# PCB_3U_DAC.net
KiCad netlist of a schematic drawn in Altium Designer
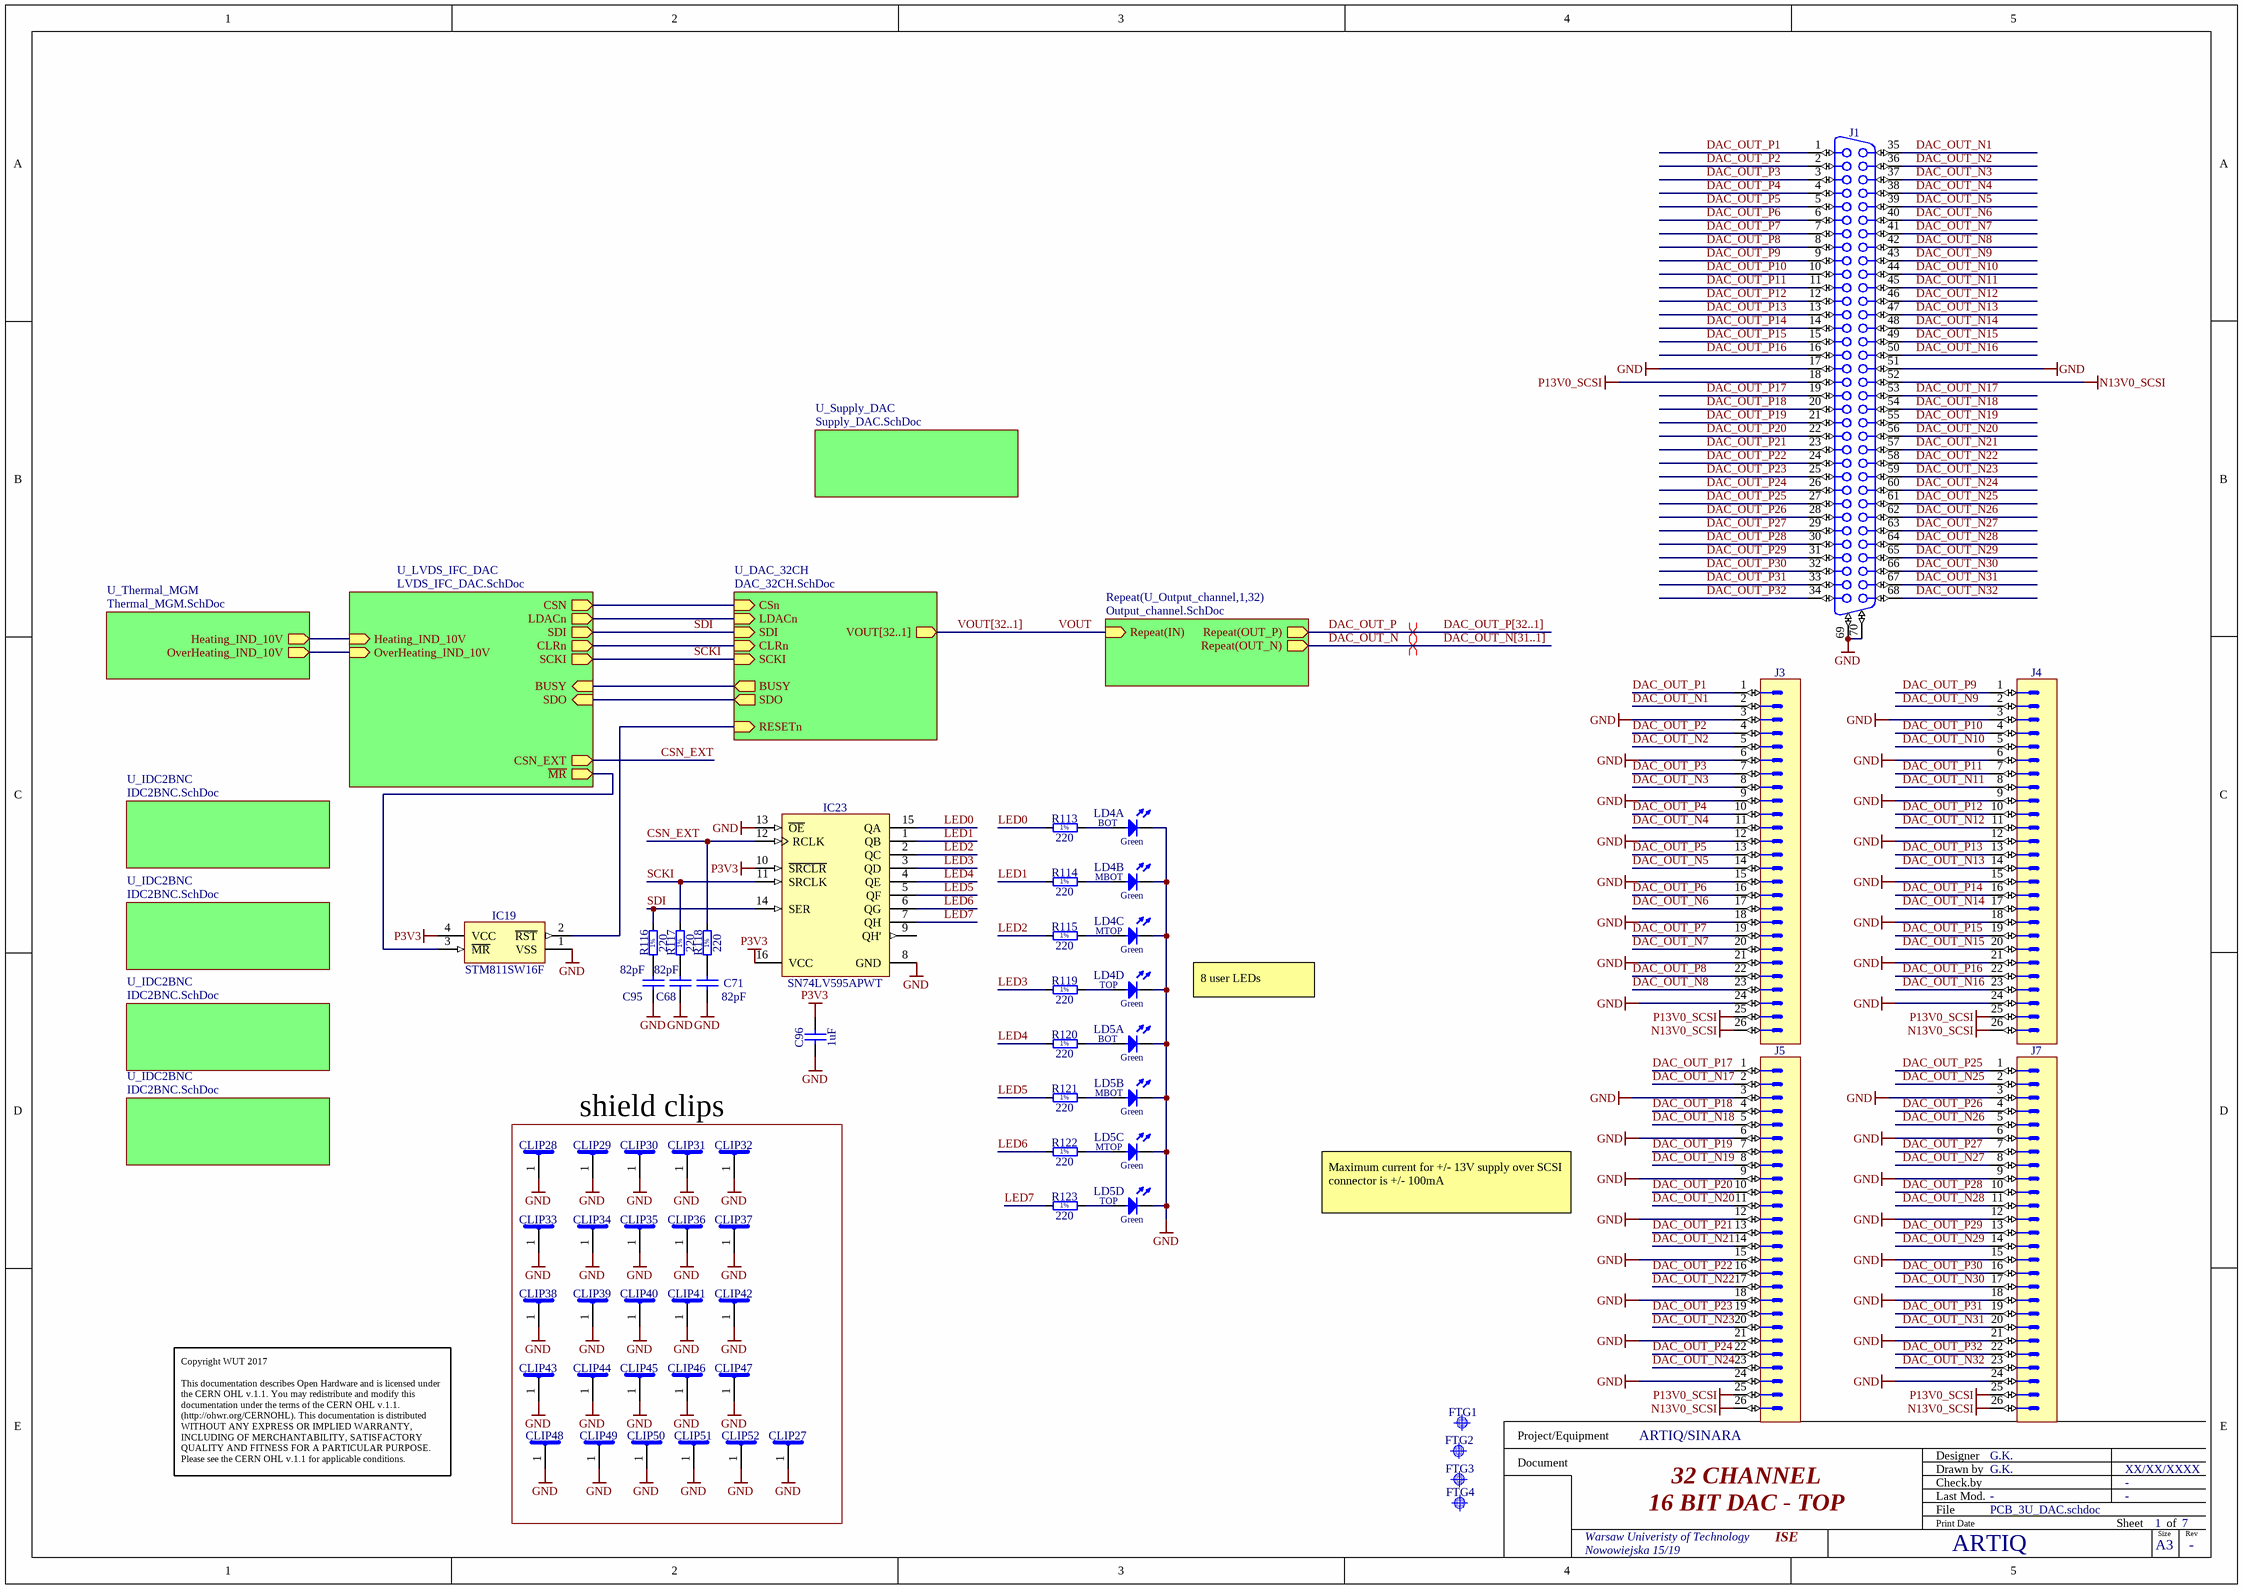
[diagram p0: PCB_3U_DAC.schdoc]

(export (version "E")
  (design (tool "Eeschema 10.0.6"))
  (components
    (comp (ref "C68")
      (value "82pF")
      (footprint "CAPC1608X87N")
      (description "Non-polarised capacitor")
      (fields
        (field (name "PART NUMBER") "CC0603_82PF_50V_5%_NP0")
        (field (name "VOLTAGE") "50V")
        (field (name "AUTHOR") "CERN DEM JLC")
      )
      (libsource (lib "Capacitors") (part "Capacitor - non polarized"))
    )
    (comp (ref "C71")
      (value "82pF")
      (footprint "CAPC1608X87N")
      (description "Non-polarised capacitor")
      (fields
        (field (name "PART NUMBER") "CC0603_82PF_50V_5%_NP0")
        (field (name "VOLTAGE") "50V")
        (field (name "AUTHOR") "CERN DEM JLC")
      )
      (libsource (lib "Capacitors") (part "Capacitor - non polarized"))
    )
    (comp (ref "C95")
      (value "82pF")
      (footprint "CAPC1608X87N")
      (description "Non-polarised capacitor")
      (fields
        (field (name "PART NUMBER") "CC0603_82PF_50V_5%_NP0")
        (field (name "VOLTAGE") "50V")
        (field (name "AUTHOR") "CERN DEM JLC")
      )
      (libsource (lib "Capacitors") (part "Capacitor - non polarized"))
    )
    (comp (ref "C96")
      (value "1uF")
      (footprint "CAPC1608X87N")
      (description "Non-polarised capacitor")
      (fields
        (field (name "PART NUMBER") "CC0603_1UF_25V_10%_X7R")
        (field (name "VOLTAGE") "25V")
        (field (name "AUTHOR") "CERN DEM JLC")
      )
      (libsource (lib "Capacitors") (part "Capacitor - non polarized"))
    )
    (comp (ref "CLIP27")
      (value "S1411-46R")
      (footprint "CLIP_HOLLAND-SHIELDING_LC")
      (description "Surface Mount Clip for PCB Screening Covers")
      (fields (field (name "MANUFACTURER") "HARWIN") (field (name "AUTHOR") "CERN DEM JLC"))
      (libsource (lib "LIBRARY_SCH") (part "SHIELD_CLIP"))
    )
    (comp (ref "CLIP28")
      (value "S1411-46R")
      (footprint "CLIP_HOLLAND-SHIELDING_LC")
      (description "Surface Mount Clip for PCB Screening Covers")
      (fields (field (name "MANUFACTURER") "HARWIN") (field (name "AUTHOR") "CERN DEM JLC"))
      (libsource (lib "LIBRARY_SCH") (part "SHIELD_CLIP"))
    )
    (comp (ref "CLIP29")
      (value "S1411-46R")
      (footprint "CLIP_HOLLAND-SHIELDING_LC")
      (description "Surface Mount Clip for PCB Screening Covers")
      (fields (field (name "MANUFACTURER") "HARWIN") (field (name "AUTHOR") "CERN DEM JLC"))
      (libsource (lib "LIBRARY_SCH") (part "SHIELD_CLIP"))
    )
    (comp (ref "CLIP30")
      (value "S1411-46R")
      (footprint "CLIP_HOLLAND-SHIELDING_LC")
      (description "Surface Mount Clip for PCB Screening Covers")
      (fields (field (name "MANUFACTURER") "HARWIN") (field (name "AUTHOR") "CERN DEM JLC"))
      (libsource (lib "LIBRARY_SCH") (part "SHIELD_CLIP"))
    )
    (comp (ref "CLIP31")
      (value "S1411-46R")
      (footprint "CLIP_HOLLAND-SHIELDING_LC")
      (description "Surface Mount Clip for PCB Screening Covers")
      (fields (field (name "MANUFACTURER") "HARWIN") (field (name "AUTHOR") "CERN DEM JLC"))
      (libsource (lib "LIBRARY_SCH") (part "SHIELD_CLIP"))
    )
    (comp (ref "CLIP32")
      (value "S1411-46R")
      (footprint "CLIP_HOLLAND-SHIELDING_LC")
      (description "Surface Mount Clip for PCB Screening Covers")
      (fields (field (name "MANUFACTURER") "HARWIN") (field (name "AUTHOR") "CERN DEM JLC"))
      (libsource (lib "LIBRARY_SCH") (part "SHIELD_CLIP"))
    )
    (comp (ref "CLIP33")
      (value "S1411-46R")
      (footprint "CLIP_HOLLAND-SHIELDING_LC")
      (description "Surface Mount Clip for PCB Screening Covers")
      (fields (field (name "MANUFACTURER") "HARWIN") (field (name "AUTHOR") "CERN DEM JLC"))
      (libsource (lib "LIBRARY_SCH") (part "SHIELD_CLIP"))
    )
    (comp (ref "CLIP34")
      (value "S1411-46R")
      (footprint "CLIP_HOLLAND-SHIELDING_LC")
      (description "Surface Mount Clip for PCB Screening Covers")
      (fields (field (name "MANUFACTURER") "HARWIN") (field (name "AUTHOR") "CERN DEM JLC"))
      (libsource (lib "LIBRARY_SCH") (part "SHIELD_CLIP"))
    )
    (comp (ref "CLIP35")
      (value "S1411-46R")
      (footprint "CLIP_HOLLAND-SHIELDING_LC")
      (description "Surface Mount Clip for PCB Screening Covers")
      (fields (field (name "MANUFACTURER") "HARWIN") (field (name "AUTHOR") "CERN DEM JLC"))
      (libsource (lib "LIBRARY_SCH") (part "SHIELD_CLIP"))
    )
    (comp (ref "CLIP36")
      (value "S1411-46R")
      (footprint "CLIP_HOLLAND-SHIELDING_LC")
      (description "Surface Mount Clip for PCB Screening Covers")
      (fields (field (name "MANUFACTURER") "HARWIN") (field (name "AUTHOR") "CERN DEM JLC"))
      (libsource (lib "LIBRARY_SCH") (part "SHIELD_CLIP"))
    )
    (comp (ref "CLIP37")
      (value "S1411-46R")
      (footprint "CLIP_HOLLAND-SHIELDING_LC")
      (description "Surface Mount Clip for PCB Screening Covers")
      (fields (field (name "MANUFACTURER") "HARWIN") (field (name "AUTHOR") "CERN DEM JLC"))
      (libsource (lib "LIBRARY_SCH") (part "SHIELD_CLIP"))
    )
    (comp (ref "CLIP38")
      (value "S1411-46R")
      (footprint "CLIP_HOLLAND-SHIELDING_LC")
      (description "Surface Mount Clip for PCB Screening Covers")
      (fields (field (name "MANUFACTURER") "HARWIN") (field (name "AUTHOR") "CERN DEM JLC"))
      (libsource (lib "LIBRARY_SCH") (part "SHIELD_CLIP"))
    )
    (comp (ref "CLIP39")
      (value "S1411-46R")
      (footprint "CLIP_HOLLAND-SHIELDING_LC")
      (description "Surface Mount Clip for PCB Screening Covers")
      (fields (field (name "MANUFACTURER") "HARWIN") (field (name "AUTHOR") "CERN DEM JLC"))
      (libsource (lib "LIBRARY_SCH") (part "SHIELD_CLIP"))
    )
    (comp (ref "CLIP40")
      (value "S1411-46R")
      (footprint "CLIP_HOLLAND-SHIELDING_LC")
      (description "Surface Mount Clip for PCB Screening Covers")
      (fields (field (name "MANUFACTURER") "HARWIN") (field (name "AUTHOR") "CERN DEM JLC"))
      (libsource (lib "LIBRARY_SCH") (part "SHIELD_CLIP"))
    )
    (comp (ref "CLIP41")
      (value "S1411-46R")
      (footprint "CLIP_HOLLAND-SHIELDING_LC")
      (description "Surface Mount Clip for PCB Screening Covers")
      (fields (field (name "MANUFACTURER") "HARWIN") (field (name "AUTHOR") "CERN DEM JLC"))
      (libsource (lib "LIBRARY_SCH") (part "SHIELD_CLIP"))
    )
    (comp (ref "CLIP42")
      (value "S1411-46R")
      (footprint "CLIP_HOLLAND-SHIELDING_LC")
      (description "Surface Mount Clip for PCB Screening Covers")
      (fields (field (name "MANUFACTURER") "HARWIN") (field (name "AUTHOR") "CERN DEM JLC"))
      (libsource (lib "LIBRARY_SCH") (part "SHIELD_CLIP"))
    )
    (comp (ref "CLIP43")
      (value "S1411-46R")
      (footprint "CLIP_HOLLAND-SHIELDING_LC")
      (description "Surface Mount Clip for PCB Screening Covers")
      (fields (field (name "MANUFACTURER") "HARWIN") (field (name "AUTHOR") "CERN DEM JLC"))
      (libsource (lib "LIBRARY_SCH") (part "SHIELD_CLIP"))
    )
    (comp (ref "CLIP44")
      (value "S1411-46R")
      (footprint "CLIP_HOLLAND-SHIELDING_LC")
      (description "Surface Mount Clip for PCB Screening Covers")
      (fields (field (name "MANUFACTURER") "HARWIN") (field (name "AUTHOR") "CERN DEM JLC"))
      (libsource (lib "LIBRARY_SCH") (part "SHIELD_CLIP"))
    )
    (comp (ref "CLIP45")
      (value "S1411-46R")
      (footprint "CLIP_HOLLAND-SHIELDING_LC")
      (description "Surface Mount Clip for PCB Screening Covers")
      (fields (field (name "MANUFACTURER") "HARWIN") (field (name "AUTHOR") "CERN DEM JLC"))
      (libsource (lib "LIBRARY_SCH") (part "SHIELD_CLIP"))
    )
    (comp (ref "CLIP46")
      (value "S1411-46R")
      (footprint "CLIP_HOLLAND-SHIELDING_LC")
      (description "Surface Mount Clip for PCB Screening Covers")
      (fields (field (name "MANUFACTURER") "HARWIN") (field (name "AUTHOR") "CERN DEM JLC"))
      (libsource (lib "LIBRARY_SCH") (part "SHIELD_CLIP"))
    )
    (comp (ref "CLIP47")
      (value "S1411-46R")
      (footprint "CLIP_HOLLAND-SHIELDING_LC")
      (description "Surface Mount Clip for PCB Screening Covers")
      (fields (field (name "MANUFACTURER") "HARWIN") (field (name "AUTHOR") "CERN DEM JLC"))
      (libsource (lib "LIBRARY_SCH") (part "SHIELD_CLIP"))
    )
    (comp (ref "CLIP48")
      (value "S1411-46R")
      (footprint "CLIP_HOLLAND-SHIELDING_LC")
      (description "Surface Mount Clip for PCB Screening Covers")
      (fields (field (name "MANUFACTURER") "HARWIN") (field (name "AUTHOR") "CERN DEM JLC"))
      (libsource (lib "LIBRARY_SCH") (part "SHIELD_CLIP"))
    )
    (comp (ref "CLIP49")
      (value "S1411-46R")
      (footprint "CLIP_HOLLAND-SHIELDING_LC")
      (description "Surface Mount Clip for PCB Screening Covers")
      (fields (field (name "MANUFACTURER") "HARWIN") (field (name "AUTHOR") "CERN DEM JLC"))
      (libsource (lib "LIBRARY_SCH") (part "SHIELD_CLIP"))
    )
    (comp (ref "CLIP50")
      (value "S1411-46R")
      (footprint "CLIP_HOLLAND-SHIELDING_LC")
      (description "Surface Mount Clip for PCB Screening Covers")
      (fields (field (name "MANUFACTURER") "HARWIN") (field (name "AUTHOR") "CERN DEM JLC"))
      (libsource (lib "LIBRARY_SCH") (part "SHIELD_CLIP"))
    )
    (comp (ref "CLIP51")
      (value "S1411-46R")
      (footprint "CLIP_HOLLAND-SHIELDING_LC")
      (description "Surface Mount Clip for PCB Screening Covers")
      (fields (field (name "MANUFACTURER") "HARWIN") (field (name "AUTHOR") "CERN DEM JLC"))
      (libsource (lib "LIBRARY_SCH") (part "SHIELD_CLIP"))
    )
    (comp (ref "CLIP52")
      (value "S1411-46R")
      (footprint "CLIP_HOLLAND-SHIELDING_LC")
      (description "Surface Mount Clip for PCB Screening Covers")
      (fields (field (name "MANUFACTURER") "HARWIN") (field (name "AUTHOR") "CERN DEM JLC"))
      (libsource (lib "LIBRARY_SCH") (part "SHIELD_CLIP"))
    )
    (comp (ref "FTG1")
      (value "Use only in PCB")
      (footprint "FIDUCIAL_TOP_C100-200")
      (description "Fiducial Target")
      (fields (field (name "PART NUMBER") "FIDUCIAL_TARGET_C100-200") (field (name "AUTHOR") "CERN DEM JLC"))
      (libsource (lib "Eletro-mechanical") (part "Fiducial Target"))
    )
    (comp (ref "FTG2")
      (value "Use only in PCB")
      (footprint "FIDUCIAL_TOP_S100-200")
      (description "Fiducial Target")
      (fields (field (name "PART NUMBER") "FIDUCIAL_TARGET_S100-200") (field (name "AUTHOR") "CERN DEM JLC"))
      (libsource (lib "Eletro-mechanical") (part "Fiducial Target"))
    )
    (comp (ref "FTG3")
      (value "Use only in PCB")
      (footprint "FIDUCIAL_TOP_S200-400")
      (description "Fiducial Target")
      (fields (field (name "PART NUMBER") "FIDUCIAL_TARGET_S200-400") (field (name "AUTHOR") "CERN DEM JLC"))
      (libsource (lib "Eletro-mechanical") (part "Fiducial Target"))
    )
    (comp (ref "FTG4")
      (value "Use only in PCB")
      (footprint "FIDUCIAL_TOP_S100-200")
      (description "Fiducial Target")
      (fields (field (name "PART NUMBER") "FIDUCIAL_TARGET_S100-200") (field (name "AUTHOR") "CERN DEM JLC"))
      (libsource (lib "Eletro-mechanical") (part "Fiducial Target"))
    )
    (comp (ref "IC19")
      (value "STM811SW16F")
      (footprint "SOT143N")
      (description "Microprocessor Reset Circuit")
      (fields (field (name "MANUFACTURER") "ST MICROELECTRONICS") (field (name "AUTHOR") "CERN DEM JLC"))
      (libsource (lib "ICs And Semiconductors") (part "STM811"))
    )
    (comp (ref "IC23")
      (value "SN74LV595APWT")
      (footprint "SOP65P640X120-16N")
      (description "8-Bit Shift Register With 3-State Output Register")
      (fields (field (name "MANUFACTURER") "TEXAS INSTRUMENTS") (field (name "AUTHOR") "CERN DEM JLC"))
      (libsource (lib "ICs And Semiconductors") (part "74595"))
    )
    (comp (ref "J1")
      (value "D-SUB")
      (footprint "TYCO_5787082-7")
      (description "68 contacts, AMPLIMITE .050\", Right Angled Receptacle Series III")
      (fields
        (field (name "PART NUMBER") "TYCO_5787082-7")
        (field (name "MANUFACTURER") "TYCO ELECTRONICS")
        (field (name "AUTHOR") "CERN DEM JLC")
      )
      (libsource (lib "Connectors") (part "TYCO_5787082-7"))
    )
    (comp (ref "J3")
      (value "Header 26")
      (footprint "3M_N2526-6002RB")
      (description "Connector 26 Male")
      (fields
        (field (name "PART NUMBER") "3M_N2526-6002RB")
        (field (name "MANUFACTURER") "3M")
        (field (name "AUTHOR") "CERN DEM JLC")
      )
      (libsource (lib "Connectors") (part "Connector 26 Male"))
    )
    (comp (ref "J4")
      (value "Header 26")
      (footprint "3M_N2526-6002RB")
      (description "Connector 26 Male")
      (fields
        (field (name "PART NUMBER") "3M_N2526-6002RB")
        (field (name "MANUFACTURER") "3M")
        (field (name "AUTHOR") "CERN DEM JLC")
      )
      (libsource (lib "Connectors") (part "Connector 26 Male"))
    )
    (comp (ref "J5")
      (value "Header 26")
      (footprint "3M_N2526-6002RB")
      (description "Connector 26 Male")
      (fields
        (field (name "PART NUMBER") "3M_N2526-6002RB")
        (field (name "MANUFACTURER") "3M")
        (field (name "AUTHOR") "CERN DEM JLC")
      )
      (libsource (lib "Connectors") (part "Connector 26 Male"))
    )
    (comp (ref "J7")
      (value "Header 26")
      (footprint "3M_N2526-6002RB")
      (description "Connector 26 Male")
      (fields
        (field (name "PART NUMBER") "3M_N2526-6002RB")
        (field (name "MANUFACTURER") "3M")
        (field (name "AUTHOR") "CERN DEM JLC")
      )
      (libsource (lib "Connectors") (part "Connector 26 Male"))
    )
    (comp (ref "LD4")
      (value "Green")
      (footprint "LED_BIVAR_H485CGDL")
      (description "LED x4 Green 1C2A-BOT_3C4A_5C6A_7C8A-TOP")
      (fields
        (field (name "PART NUMBER") "LED_BIVAR_H485CGDL")
        (field (name "MANUFACTURER") "BIVAR")
        (field (name "AUTHOR") "CERN DEM JLC")
      )
      (libsource (lib "ICs And Semiconductors") (part "LED x4 Green 1C2A-BOT_3C4A_5C6A_7C8A-TOP"))
    )
    (comp (ref "LD5")
      (value "Green")
      (footprint "LED_BIVAR_H485CGDL")
      (description "LED x4 Green 1C2A-BOT_3C4A_5C6A_7C8A-TOP")
      (fields
        (field (name "PART NUMBER") "LED_BIVAR_H485CGDL")
        (field (name "MANUFACTURER") "BIVAR")
        (field (name "AUTHOR") "CERN DEM JLC")
      )
      (libsource (lib "ICs And Semiconductors") (part "LED x4 Green 1C2A-BOT_3C4A_5C6A_7C8A-TOP"))
    )
    (comp (ref "R113")
      (value "220")
      (footprint "RESC1608X55N")
      (description "Resistor - 1%")
      (fields
        (field (name "PART NUMBER") "R0603_220R_1%_0.1W_100PPM")
        (field (name "POWER") "0.1W")
        (field (name "AUTHOR") "CERN DEM JLC")
      )
      (libsource (lib "Resistors") (part "Resistor - 1%"))
    )
    (comp (ref "R114")
      (value "220")
      (footprint "RESC1608X55N")
      (description "Resistor - 1%")
      (fields
        (field (name "PART NUMBER") "R0603_220R_1%_0.1W_100PPM")
        (field (name "POWER") "0.1W")
        (field (name "AUTHOR") "CERN DEM JLC")
      )
      (libsource (lib "Resistors") (part "Resistor - 1%"))
    )
    (comp (ref "R115")
      (value "220")
      (footprint "RESC1608X55N")
      (description "Resistor - 1%")
      (fields
        (field (name "PART NUMBER") "R0603_220R_1%_0.1W_100PPM")
        (field (name "POWER") "0.1W")
        (field (name "AUTHOR") "CERN DEM JLC")
      )
      (libsource (lib "Resistors") (part "Resistor - 1%"))
    )
    (comp (ref "R116")
      (value "220")
      (footprint "RESC1608X55N")
      (description "Resistor - 1%")
      (fields
        (field (name "PART NUMBER") "R0603_220R_1%_0.1W_100PPM")
        (field (name "POWER") "0.1W")
        (field (name "AUTHOR") "CERN DEM JLC")
      )
      (libsource (lib "Resistors") (part "Resistor - 1%"))
    )
    (comp (ref "R117")
      (value "220")
      (footprint "RESC1608X55N")
      (description "Resistor - 1%")
      (fields
        (field (name "PART NUMBER") "R0603_220R_1%_0.1W_100PPM")
        (field (name "POWER") "0.1W")
        (field (name "AUTHOR") "CERN DEM JLC")
      )
      (libsource (lib "Resistors") (part "Resistor - 1%"))
    )
    (comp (ref "R118")
      (value "220")
      (footprint "RESC1608X55N")
      (description "Resistor - 1%")
      (fields
        (field (name "PART NUMBER") "R0603_220R_1%_0.1W_100PPM")
        (field (name "POWER") "0.1W")
        (field (name "AUTHOR") "CERN DEM JLC")
      )
      (libsource (lib "Resistors") (part "Resistor - 1%"))
    )
    (comp (ref "R119")
      (value "220")
      (footprint "RESC1608X55N")
      (description "Resistor - 1%")
      (fields
        (field (name "PART NUMBER") "R0603_220R_1%_0.1W_100PPM")
        (field (name "POWER") "0.1W")
        (field (name "AUTHOR") "CERN DEM JLC")
      )
      (libsource (lib "Resistors") (part "Resistor - 1%"))
    )
    (comp (ref "R120")
      (value "220")
      (footprint "RESC1608X55N")
      (description "Resistor - 1%")
      (fields
        (field (name "PART NUMBER") "R0603_220R_1%_0.1W_100PPM")
        (field (name "POWER") "0.1W")
        (field (name "AUTHOR") "CERN DEM JLC")
      )
      (libsource (lib "Resistors") (part "Resistor - 1%"))
    )
    (comp (ref "R121")
      (value "220")
      (footprint "RESC1608X55N")
      (description "Resistor - 1%")
      (fields
        (field (name "PART NUMBER") "R0603_220R_1%_0.1W_100PPM")
        (field (name "POWER") "0.1W")
        (field (name "AUTHOR") "CERN DEM JLC")
      )
      (libsource (lib "Resistors") (part "Resistor - 1%"))
    )
    (comp (ref "R122")
      (value "220")
      (footprint "RESC1608X55N")
      (description "Resistor - 1%")
      (fields
        (field (name "PART NUMBER") "R0603_220R_1%_0.1W_100PPM")
        (field (name "POWER") "0.1W")
        (field (name "AUTHOR") "CERN DEM JLC")
      )
      (libsource (lib "Resistors") (part "Resistor - 1%"))
    )
    (comp (ref "R123")
      (value "220")
      (footprint "RESC1608X55N")
      (description "Resistor - 1%")
      (fields
        (field (name "PART NUMBER") "R0603_220R_1%_0.1W_100PPM")
        (field (name "POWER") "0.1W")
        (field (name "AUTHOR") "CERN DEM JLC")
      )
      (libsource (lib "Resistors") (part "Resistor - 1%"))
    )
  )
  (nets
    (net (code "36") (name "/CSN_EXT") (class "Default")
      (node (ref "IC23") (pin "12") (pinfunction "RCLK_12") (pintype "input"))
      (node (ref "R118") (pin "2") (pinfunction "2_2") (pintype "passive"))
    )
    (net (code "38") (name "/DAC_OUT_N1") (class "Default")
      (node (ref "J1") (pin "35") (pinfunction "35_35") (pintype "bidirectional"))
      (node (ref "J3") (pin "2") (pinfunction "2_2") (pintype "bidirectional"))
    )
    (net (code "39") (name "/DAC_OUT_N2") (class "Default")
      (node (ref "J1") (pin "36") (pinfunction "36_36") (pintype "bidirectional"))
      (node (ref "J3") (pin "5") (pinfunction "5_5") (pintype "bidirectional"))
    )
    (net (code "40") (name "/DAC_OUT_N3") (class "Default")
      (node (ref "J1") (pin "37") (pinfunction "37_37") (pintype "bidirectional"))
      (node (ref "J3") (pin "8") (pinfunction "8_8") (pintype "bidirectional"))
    )
    (net (code "41") (name "/DAC_OUT_N4") (class "Default")
      (node (ref "J1") (pin "38") (pinfunction "38_38") (pintype "bidirectional"))
      (node (ref "J3") (pin "11") (pinfunction "11_11") (pintype "bidirectional"))
    )
    (net (code "42") (name "/DAC_OUT_N5") (class "Default")
      (node (ref "J1") (pin "39") (pinfunction "39_39") (pintype "bidirectional"))
      (node (ref "J3") (pin "14") (pinfunction "14_14") (pintype "bidirectional"))
    )
    (net (code "43") (name "/DAC_OUT_N6") (class "Default")
      (node (ref "J1") (pin "40") (pinfunction "40_40") (pintype "bidirectional"))
      (node (ref "J3") (pin "17") (pinfunction "17_17") (pintype "bidirectional"))
    )
    (net (code "44") (name "/DAC_OUT_N7") (class "Default")
      (node (ref "J1") (pin "41") (pinfunction "41_41") (pintype "bidirectional"))
      (node (ref "J3") (pin "20") (pinfunction "20_20") (pintype "bidirectional"))
    )
    (net (code "45") (name "/DAC_OUT_N8") (class "Default")
      (node (ref "J1") (pin "42") (pinfunction "42_42") (pintype "bidirectional"))
      (node (ref "J3") (pin "23") (pinfunction "23_23") (pintype "bidirectional"))
    )
    (net (code "46") (name "/DAC_OUT_N9") (class "Default")
      (node (ref "J1") (pin "43") (pinfunction "43_43") (pintype "bidirectional"))
      (node (ref "J4") (pin "2") (pinfunction "2_2") (pintype "bidirectional"))
    )
    (net (code "47") (name "/DAC_OUT_N10") (class "Default")
      (node (ref "J1") (pin "44") (pinfunction "44_44") (pintype "bidirectional"))
      (node (ref "J4") (pin "5") (pinfunction "5_5") (pintype "bidirectional"))
    )
    (net (code "48") (name "/DAC_OUT_N11") (class "Default")
      (node (ref "J1") (pin "45") (pinfunction "45_45") (pintype "bidirectional"))
      (node (ref "J4") (pin "8") (pinfunction "8_8") (pintype "bidirectional"))
    )
    (net (code "49") (name "/DAC_OUT_N12") (class "Default")
      (node (ref "J1") (pin "46") (pinfunction "46_46") (pintype "bidirectional"))
      (node (ref "J4") (pin "11") (pinfunction "11_11") (pintype "bidirectional"))
    )
    (net (code "50") (name "/DAC_OUT_N13") (class "Default")
      (node (ref "J1") (pin "47") (pinfunction "47_47") (pintype "bidirectional"))
      (node (ref "J4") (pin "14") (pinfunction "14_14") (pintype "bidirectional"))
    )
    (net (code "51") (name "/DAC_OUT_N14") (class "Default")
      (node (ref "J1") (pin "48") (pinfunction "48_48") (pintype "bidirectional"))
      (node (ref "J4") (pin "17") (pinfunction "17_17") (pintype "bidirectional"))
    )
    (net (code "52") (name "/DAC_OUT_N15") (class "Default")
      (node (ref "J1") (pin "49") (pinfunction "49_49") (pintype "bidirectional"))
      (node (ref "J4") (pin "20") (pinfunction "20_20") (pintype "bidirectional"))
    )
    (net (code "53") (name "/DAC_OUT_N16") (class "Default")
      (node (ref "J1") (pin "50") (pinfunction "50_50") (pintype "bidirectional"))
      (node (ref "J4") (pin "23") (pinfunction "23_23") (pintype "bidirectional"))
    )
    (net (code "54") (name "/DAC_OUT_N17") (class "Default")
      (node (ref "J1") (pin "53") (pinfunction "53_53") (pintype "bidirectional"))
      (node (ref "J5") (pin "2") (pinfunction "2_2") (pintype "bidirectional"))
    )
    (net (code "55") (name "/DAC_OUT_N18") (class "Default")
      (node (ref "J1") (pin "54") (pinfunction "54_54") (pintype "bidirectional"))
      (node (ref "J5") (pin "5") (pinfunction "5_5") (pintype "bidirectional"))
    )
    (net (code "56") (name "/DAC_OUT_N19") (class "Default")
      (node (ref "J1") (pin "55") (pinfunction "55_55") (pintype "bidirectional"))
      (node (ref "J5") (pin "8") (pinfunction "8_8") (pintype "bidirectional"))
    )
    (net (code "57") (name "/DAC_OUT_N20") (class "Default")
      (node (ref "J1") (pin "56") (pinfunction "56_56") (pintype "bidirectional"))
      (node (ref "J5") (pin "11") (pinfunction "11_11") (pintype "bidirectional"))
    )
    (net (code "58") (name "/DAC_OUT_N21") (class "Default")
      (node (ref "J1") (pin "57") (pinfunction "57_57") (pintype "bidirectional"))
      (node (ref "J5") (pin "14") (pinfunction "14_14") (pintype "bidirectional"))
    )
    (net (code "59") (name "/DAC_OUT_N22") (class "Default")
      (node (ref "J1") (pin "58") (pinfunction "58_58") (pintype "bidirectional"))
      (node (ref "J5") (pin "17") (pinfunction "17_17") (pintype "bidirectional"))
    )
    (net (code "60") (name "/DAC_OUT_N23") (class "Default")
      (node (ref "J1") (pin "59") (pinfunction "59_59") (pintype "bidirectional"))
      (node (ref "J5") (pin "20") (pinfunction "20_20") (pintype "bidirectional"))
    )
    (net (code "61") (name "/DAC_OUT_N24") (class "Default")
      (node (ref "J1") (pin "60") (pinfunction "60_60") (pintype "bidirectional"))
      (node (ref "J5") (pin "23") (pinfunction "23_23") (pintype "bidirectional"))
    )
    (net (code "62") (name "/DAC_OUT_N25") (class "Default")
      (node (ref "J1") (pin "61") (pinfunction "61_61") (pintype "bidirectional"))
      (node (ref "J7") (pin "2") (pinfunction "2_2") (pintype "bidirectional"))
    )
    (net (code "63") (name "/DAC_OUT_N26") (class "Default")
      (node (ref "J1") (pin "62") (pinfunction "62_62") (pintype "bidirectional"))
      (node (ref "J7") (pin "5") (pinfunction "5_5") (pintype "bidirectional"))
    )
    (net (code "64") (name "/DAC_OUT_N27") (class "Default")
      (node (ref "J1") (pin "63") (pinfunction "63_63") (pintype "bidirectional"))
      (node (ref "J7") (pin "8") (pinfunction "8_8") (pintype "bidirectional"))
    )
    (net (code "65") (name "/DAC_OUT_N28") (class "Default")
      (node (ref "J1") (pin "64") (pinfunction "64_64") (pintype "bidirectional"))
      (node (ref "J7") (pin "11") (pinfunction "11_11") (pintype "bidirectional"))
    )
    (net (code "66") (name "/DAC_OUT_N29") (class "Default")
      (node (ref "J1") (pin "65") (pinfunction "65_65") (pintype "bidirectional"))
      (node (ref "J7") (pin "14") (pinfunction "14_14") (pintype "bidirectional"))
    )
    (net (code "67") (name "/DAC_OUT_N30") (class "Default")
      (node (ref "J1") (pin "66") (pinfunction "66_66") (pintype "bidirectional"))
      (node (ref "J7") (pin "17") (pinfunction "17_17") (pintype "bidirectional"))
    )
    (net (code "68") (name "/DAC_OUT_N31") (class "Default")
      (node (ref "J1") (pin "67") (pinfunction "67_67") (pintype "bidirectional"))
      (node (ref "J7") (pin "20") (pinfunction "20_20") (pintype "bidirectional"))
    )
    (net (code "69") (name "/DAC_OUT_N32") (class "Default")
      (node (ref "J1") (pin "68") (pinfunction "68_68") (pintype "bidirectional"))
      (node (ref "J7") (pin "23") (pinfunction "23_23") (pintype "bidirectional"))
    )
    (net (code "72") (name "/DAC_OUT_P1") (class "Default")
      (node (ref "J1") (pin "1") (pinfunction "1_1") (pintype "bidirectional"))
      (node (ref "J3") (pin "1") (pinfunction "1_1") (pintype "bidirectional"))
    )
    (net (code "73") (name "/DAC_OUT_P2") (class "Default")
      (node (ref "J1") (pin "2") (pinfunction "2_2") (pintype "bidirectional"))
      (node (ref "J3") (pin "4") (pinfunction "4_4") (pintype "bidirectional"))
    )
    (net (code "74") (name "/DAC_OUT_P3") (class "Default")
      (node (ref "J1") (pin "3") (pinfunction "3_3") (pintype "bidirectional"))
      (node (ref "J3") (pin "7") (pinfunction "7_7") (pintype "bidirectional"))
    )
    (net (code "75") (name "/DAC_OUT_P4") (class "Default")
      (node (ref "J1") (pin "4") (pinfunction "4_4") (pintype "bidirectional"))
      (node (ref "J3") (pin "10") (pinfunction "10_10") (pintype "bidirectional"))
    )
    (net (code "76") (name "/DAC_OUT_P5") (class "Default")
      (node (ref "J1") (pin "5") (pinfunction "5_5") (pintype "bidirectional"))
      (node (ref "J3") (pin "13") (pinfunction "13_13") (pintype "bidirectional"))
    )
    (net (code "77") (name "/DAC_OUT_P6") (class "Default")
      (node (ref "J1") (pin "6") (pinfunction "6_6") (pintype "bidirectional"))
      (node (ref "J3") (pin "16") (pinfunction "16_16") (pintype "bidirectional"))
    )
    (net (code "78") (name "/DAC_OUT_P7") (class "Default")
      (node (ref "J1") (pin "7") (pinfunction "7_7") (pintype "bidirectional"))
      (node (ref "J3") (pin "19") (pinfunction "19_19") (pintype "bidirectional"))
    )
    (net (code "79") (name "/DAC_OUT_P8") (class "Default")
      (node (ref "J1") (pin "8") (pinfunction "8_8") (pintype "bidirectional"))
      (node (ref "J3") (pin "22") (pinfunction "22_22") (pintype "bidirectional"))
    )
    (net (code "80") (name "/DAC_OUT_P9") (class "Default")
      (node (ref "J1") (pin "9") (pinfunction "9_9") (pintype "bidirectional"))
      (node (ref "J4") (pin "1") (pinfunction "1_1") (pintype "bidirectional"))
    )
    (net (code "81") (name "/DAC_OUT_P10") (class "Default")
      (node (ref "J1") (pin "10") (pinfunction "10_10") (pintype "bidirectional"))
      (node (ref "J4") (pin "4") (pinfunction "4_4") (pintype "bidirectional"))
    )
    (net (code "82") (name "/DAC_OUT_P11") (class "Default")
      (node (ref "J1") (pin "11") (pinfunction "11_11") (pintype "bidirectional"))
      (node (ref "J4") (pin "7") (pinfunction "7_7") (pintype "bidirectional"))
    )
    (net (code "83") (name "/DAC_OUT_P12") (class "Default")
      (node (ref "J1") (pin "12") (pinfunction "12_12") (pintype "bidirectional"))
      (node (ref "J4") (pin "10") (pinfunction "10_10") (pintype "bidirectional"))
    )
    (net (code "84") (name "/DAC_OUT_P13") (class "Default")
      (node (ref "J1") (pin "13") (pinfunction "13_13") (pintype "bidirectional"))
      (node (ref "J4") (pin "13") (pinfunction "13_13") (pintype "bidirectional"))
    )
    (net (code "85") (name "/DAC_OUT_P14") (class "Default")
      (node (ref "J1") (pin "14") (pinfunction "14_14") (pintype "bidirectional"))
      (node (ref "J4") (pin "16") (pinfunction "16_16") (pintype "bidirectional"))
    )
    (net (code "86") (name "/DAC_OUT_P15") (class "Default")
      (node (ref "J1") (pin "15") (pinfunction "15_15") (pintype "bidirectional"))
      (node (ref "J4") (pin "19") (pinfunction "19_19") (pintype "bidirectional"))
    )
    (net (code "87") (name "/DAC_OUT_P16") (class "Default")
      (node (ref "J1") (pin "16") (pinfunction "16_16") (pintype "bidirectional"))
      (node (ref "J4") (pin "22") (pinfunction "22_22") (pintype "bidirectional"))
    )
    (net (code "88") (name "/DAC_OUT_P17") (class "Default")
      (node (ref "J1") (pin "19") (pinfunction "19_19") (pintype "bidirectional"))
      (node (ref "J5") (pin "1") (pinfunction "1_1") (pintype "bidirectional"))
    )
    (net (code "89") (name "/DAC_OUT_P18") (class "Default")
      (node (ref "J1") (pin "20") (pinfunction "20_20") (pintype "bidirectional"))
      (node (ref "J5") (pin "4") (pinfunction "4_4") (pintype "bidirectional"))
    )
    (net (code "90") (name "/DAC_OUT_P19") (class "Default")
      (node (ref "J1") (pin "21") (pinfunction "21_21") (pintype "bidirectional"))
      (node (ref "J5") (pin "7") (pinfunction "7_7") (pintype "bidirectional"))
    )
    (net (code "91") (name "/DAC_OUT_P20") (class "Default")
      (node (ref "J1") (pin "22") (pinfunction "22_22") (pintype "bidirectional"))
      (node (ref "J5") (pin "10") (pinfunction "10_10") (pintype "bidirectional"))
    )
    (net (code "92") (name "/DAC_OUT_P21") (class "Default")
      (node (ref "J1") (pin "23") (pinfunction "23_23") (pintype "bidirectional"))
      (node (ref "J5") (pin "13") (pinfunction "13_13") (pintype "bidirectional"))
    )
    (net (code "93") (name "/DAC_OUT_P22") (class "Default")
      (node (ref "J1") (pin "24") (pinfunction "24_24") (pintype "bidirectional"))
      (node (ref "J5") (pin "16") (pinfunction "16_16") (pintype "bidirectional"))
    )
    (net (code "94") (name "/DAC_OUT_P23") (class "Default")
      (node (ref "J1") (pin "25") (pinfunction "25_25") (pintype "bidirectional"))
      (node (ref "J5") (pin "19") (pinfunction "19_19") (pintype "bidirectional"))
    )
    (net (code "95") (name "/DAC_OUT_P24") (class "Default")
      (node (ref "J1") (pin "26") (pinfunction "26_26") (pintype "bidirectional"))
      (node (ref "J5") (pin "22") (pinfunction "22_22") (pintype "bidirectional"))
    )
    (net (code "96") (name "/DAC_OUT_P25") (class "Default")
      (node (ref "J1") (pin "27") (pinfunction "27_27") (pintype "bidirectional"))
      (node (ref "J7") (pin "1") (pinfunction "1_1") (pintype "bidirectional"))
    )
    (net (code "97") (name "/DAC_OUT_P26") (class "Default")
      (node (ref "J1") (pin "28") (pinfunction "28_28") (pintype "bidirectional"))
      (node (ref "J7") (pin "4") (pinfunction "4_4") (pintype "bidirectional"))
    )
    (net (code "98") (name "/DAC_OUT_P27") (class "Default")
      (node (ref "J1") (pin "29") (pinfunction "29_29") (pintype "bidirectional"))
      (node (ref "J7") (pin "7") (pinfunction "7_7") (pintype "bidirectional"))
    )
    (net (code "99") (name "/DAC_OUT_P28") (class "Default")
      (node (ref "J1") (pin "30") (pinfunction "30_30") (pintype "bidirectional"))
      (node (ref "J7") (pin "10") (pinfunction "10_10") (pintype "bidirectional"))
    )
    (net (code "100") (name "/DAC_OUT_P29") (class "Default")
      (node (ref "J1") (pin "31") (pinfunction "31_31") (pintype "bidirectional"))
      (node (ref "J7") (pin "13") (pinfunction "13_13") (pintype "bidirectional"))
    )
    (net (code "101") (name "/DAC_OUT_P30") (class "Default")
      (node (ref "J1") (pin "32") (pinfunction "32_32") (pintype "bidirectional"))
      (node (ref "J7") (pin "16") (pinfunction "16_16") (pintype "bidirectional"))
    )
    (net (code "102") (name "/DAC_OUT_P31") (class "Default")
      (node (ref "J1") (pin "33") (pinfunction "33_33") (pintype "bidirectional"))
      (node (ref "J7") (pin "19") (pinfunction "19_19") (pintype "bidirectional"))
    )
    (net (code "103") (name "/DAC_OUT_P32") (class "Default")
      (node (ref "J1") (pin "34") (pinfunction "34_34") (pintype "bidirectional"))
      (node (ref "J7") (pin "22") (pinfunction "22_22") (pintype "bidirectional"))
    )
    (net (code "107") (name "/LED0") (class "Default")
      (node (ref "IC23") (pin "15") (pinfunction "QA_15") (pintype "tri_state"))
      (node (ref "R113") (pin "1") (pinfunction "1_1") (pintype "passive"))
    )
    (net (code "108") (name "/LED1") (class "Default")
      (node (ref "IC23") (pin "1") (pinfunction "QB_1") (pintype "tri_state"))
      (node (ref "R114") (pin "1") (pinfunction "1_1") (pintype "passive"))
    )
    (net (code "109") (name "/LED2") (class "Default")
      (node (ref "IC23") (pin "2") (pinfunction "QC_2") (pintype "tri_state"))
      (node (ref "R115") (pin "1") (pinfunction "1_1") (pintype "passive"))
    )
    (net (code "110") (name "/LED3") (class "Default")
      (node (ref "IC23") (pin "3") (pinfunction "QD_3") (pintype "tri_state"))
      (node (ref "R119") (pin "1") (pinfunction "1_1") (pintype "passive"))
    )
    (net (code "111") (name "/LED4") (class "Default")
      (node (ref "IC23") (pin "4") (pinfunction "QE_4") (pintype "tri_state"))
      (node (ref "R120") (pin "1") (pinfunction "1_1") (pintype "passive"))
    )
    (net (code "112") (name "/LED5") (class "Default")
      (node (ref "IC23") (pin "5") (pinfunction "QF_5") (pintype "tri_state"))
      (node (ref "R121") (pin "1") (pinfunction "1_1") (pintype "passive"))
    )
    (net (code "113") (name "/LED6") (class "Default")
      (node (ref "IC23") (pin "6") (pinfunction "QG_6") (pintype "tri_state"))
      (node (ref "R122") (pin "1") (pinfunction "1_1") (pintype "passive"))
    )
    (net (code "114") (name "/LED7") (class "Default")
      (node (ref "IC23") (pin "7") (pinfunction "QH_7") (pintype "tri_state"))
      (node (ref "R123") (pin "1") (pinfunction "1_1") (pintype "passive"))
    )
    (net (code "116") (name "/RESETn") (class "Default")
      (node (ref "IC19") (pin "2") (pinfunction "~{RST}_2") (pintype "output"))
    )
    (net (code "117") (name "/SCKI") (class "Default")
      (node (ref "IC23") (pin "11") (pinfunction "SRCLK_11") (pintype "input"))
      (node (ref "R117") (pin "2") (pinfunction "2_2") (pintype "passive"))
    )
    (net (code "118") (name "/SDI") (class "Default")
      (node (ref "IC23") (pin "14") (pinfunction "SER_14") (pintype "input"))
      (node (ref "R116") (pin "2") (pinfunction "2_2") (pintype "passive"))
    )
    (net (code "122") (name "/~{MR}") (class "Default")
      (node (ref "IC19") (pin "3") (pinfunction "~{MR}_3") (pintype "input"))
    )
    (net (code "123") (name "GND") (class "Default")
      (node (ref "C68") (pin "1") (pinfunction "1_1") (pintype "passive"))
      (node (ref "C71") (pin "1") (pinfunction "1_1") (pintype "passive"))
      (node (ref "C95") (pin "1") (pinfunction "1_1") (pintype "passive"))
      (node (ref "C96") (pin "1") (pinfunction "1_1") (pintype "passive"))
      (node (ref "CLIP27") (pin "1") (pinfunction "1_1") (pintype "passive"))
      (node (ref "CLIP28") (pin "1") (pinfunction "1_1") (pintype "passive"))
      (node (ref "CLIP29") (pin "1") (pinfunction "1_1") (pintype "passive"))
      (node (ref "CLIP30") (pin "1") (pinfunction "1_1") (pintype "passive"))
      (node (ref "CLIP31") (pin "1") (pinfunction "1_1") (pintype "passive"))
      (node (ref "CLIP32") (pin "1") (pinfunction "1_1") (pintype "passive"))
      (node (ref "CLIP33") (pin "1") (pinfunction "1_1") (pintype "passive"))
      (node (ref "CLIP34") (pin "1") (pinfunction "1_1") (pintype "passive"))
      (node (ref "CLIP35") (pin "1") (pinfunction "1_1") (pintype "passive"))
      (node (ref "CLIP36") (pin "1") (pinfunction "1_1") (pintype "passive"))
      (node (ref "CLIP37") (pin "1") (pinfunction "1_1") (pintype "passive"))
      (node (ref "CLIP38") (pin "1") (pinfunction "1_1") (pintype "passive"))
      (node (ref "CLIP39") (pin "1") (pinfunction "1_1") (pintype "passive"))
      (node (ref "CLIP40") (pin "1") (pinfunction "1_1") (pintype "passive"))
      (node (ref "CLIP41") (pin "1") (pinfunction "1_1") (pintype "passive"))
      (node (ref "CLIP42") (pin "1") (pinfunction "1_1") (pintype "passive"))
      (node (ref "CLIP43") (pin "1") (pinfunction "1_1") (pintype "passive"))
      (node (ref "CLIP44") (pin "1") (pinfunction "1_1") (pintype "passive"))
      (node (ref "CLIP45") (pin "1") (pinfunction "1_1") (pintype "passive"))
      (node (ref "CLIP46") (pin "1") (pinfunction "1_1") (pintype "passive"))
      (node (ref "CLIP47") (pin "1") (pinfunction "1_1") (pintype "passive"))
      (node (ref "CLIP48") (pin "1") (pinfunction "1_1") (pintype "passive"))
      (node (ref "CLIP49") (pin "1") (pinfunction "1_1") (pintype "passive"))
      (node (ref "CLIP50") (pin "1") (pinfunction "1_1") (pintype "passive"))
      (node (ref "CLIP51") (pin "1") (pinfunction "1_1") (pintype "passive"))
      (node (ref "CLIP52") (pin "1") (pinfunction "1_1") (pintype "passive"))
      (node (ref "IC19") (pin "1") (pinfunction "VSS_1") (pintype "power_in"))
      (node (ref "IC23") (pin "13") (pinfunction "~{OE}_13") (pintype "input"))
      (node (ref "IC23") (pin "8") (pinfunction "GND_8") (pintype "power_in"))
      (node (ref "J1") (pin "17") (pinfunction "17_17") (pintype "bidirectional"))
      (node (ref "J1") (pin "51") (pinfunction "51_51") (pintype "bidirectional"))
      (node (ref "J1") (pin "69") (pinfunction "69_69") (pintype "bidirectional"))
      (node (ref "J1") (pin "70") (pinfunction "70_70") (pintype "bidirectional"))
      (node (ref "J3") (pin "12") (pinfunction "12_12") (pintype "bidirectional"))
      (node (ref "J3") (pin "15") (pinfunction "15_15") (pintype "bidirectional"))
      (node (ref "J3") (pin "18") (pinfunction "18_18") (pintype "bidirectional"))
      (node (ref "J3") (pin "21") (pinfunction "21_21") (pintype "bidirectional"))
      (node (ref "J3") (pin "24") (pinfunction "24_24") (pintype "bidirectional"))
      (node (ref "J3") (pin "3") (pinfunction "3_3") (pintype "bidirectional"))
      (node (ref "J3") (pin "6") (pinfunction "6_6") (pintype "bidirectional"))
      (node (ref "J3") (pin "9") (pinfunction "9_9") (pintype "bidirectional"))
      (node (ref "J4") (pin "12") (pinfunction "12_12") (pintype "bidirectional"))
      (node (ref "J4") (pin "15") (pinfunction "15_15") (pintype "bidirectional"))
      (node (ref "J4") (pin "18") (pinfunction "18_18") (pintype "bidirectional"))
      (node (ref "J4") (pin "21") (pinfunction "21_21") (pintype "bidirectional"))
      (node (ref "J4") (pin "24") (pinfunction "24_24") (pintype "bidirectional"))
      (node (ref "J4") (pin "3") (pinfunction "3_3") (pintype "bidirectional"))
      (node (ref "J4") (pin "6") (pinfunction "6_6") (pintype "bidirectional"))
      (node (ref "J4") (pin "9") (pinfunction "9_9") (pintype "bidirectional"))
      (node (ref "J5") (pin "12") (pinfunction "12_12") (pintype "bidirectional"))
      (node (ref "J5") (pin "15") (pinfunction "15_15") (pintype "bidirectional"))
      (node (ref "J5") (pin "18") (pinfunction "18_18") (pintype "bidirectional"))
      (node (ref "J5") (pin "21") (pinfunction "21_21") (pintype "bidirectional"))
      (node (ref "J5") (pin "24") (pinfunction "24_24") (pintype "bidirectional"))
      (node (ref "J5") (pin "3") (pinfunction "3_3") (pintype "bidirectional"))
      (node (ref "J5") (pin "6") (pinfunction "6_6") (pintype "bidirectional"))
      (node (ref "J5") (pin "9") (pinfunction "9_9") (pintype "bidirectional"))
      (node (ref "J7") (pin "12") (pinfunction "12_12") (pintype "bidirectional"))
      (node (ref "J7") (pin "15") (pinfunction "15_15") (pintype "bidirectional"))
      (node (ref "J7") (pin "18") (pinfunction "18_18") (pintype "bidirectional"))
      (node (ref "J7") (pin "21") (pinfunction "21_21") (pintype "bidirectional"))
      (node (ref "J7") (pin "24") (pinfunction "24_24") (pintype "bidirectional"))
      (node (ref "J7") (pin "3") (pinfunction "3_3") (pintype "bidirectional"))
      (node (ref "J7") (pin "6") (pinfunction "6_6") (pintype "bidirectional"))
      (node (ref "J7") (pin "9") (pinfunction "9_9") (pintype "bidirectional"))
      (node (ref "LD4") (pin "1") (pinfunction "C_1") (pintype "passive"))
      (node (ref "LD4") (pin "3") (pinfunction "C_3") (pintype "passive"))
      (node (ref "LD4") (pin "5") (pinfunction "C_5") (pintype "passive"))
      (node (ref "LD4") (pin "7") (pinfunction "C_7") (pintype "passive"))
      (node (ref "LD5") (pin "1") (pinfunction "C_1") (pintype "passive"))
      (node (ref "LD5") (pin "3") (pinfunction "C_3") (pintype "passive"))
      (node (ref "LD5") (pin "5") (pinfunction "C_5") (pintype "passive"))
      (node (ref "LD5") (pin "7") (pinfunction "C_7") (pintype "passive"))
    )
    (net (code "124") (name "N13V0_SCSI") (class "Default")
      (node (ref "J1") (pin "52") (pinfunction "52_52") (pintype "bidirectional"))
      (node (ref "J3") (pin "26") (pinfunction "26_26") (pintype "bidirectional"))
      (node (ref "J4") (pin "26") (pinfunction "26_26") (pintype "bidirectional"))
      (node (ref "J5") (pin "26") (pinfunction "26_26") (pintype "bidirectional"))
      (node (ref "J7") (pin "26") (pinfunction "26_26") (pintype "bidirectional"))
    )
    (net (code "125") (name "Net-(C68-Pad2)") (class "Default")
      (node (ref "C68") (pin "2") (pinfunction "2_2") (pintype "passive"))
      (node (ref "R117") (pin "1") (pinfunction "1_1") (pintype "passive"))
    )
    (net (code "126") (name "Net-(C71-Pad2)") (class "Default")
      (node (ref "C71") (pin "2") (pinfunction "2_2") (pintype "passive"))
      (node (ref "R118") (pin "1") (pinfunction "1_1") (pintype "passive"))
    )
    (net (code "127") (name "Net-(C95-Pad2)") (class "Default")
      (node (ref "C95") (pin "2") (pinfunction "2_2") (pintype "passive"))
      (node (ref "R116") (pin "1") (pinfunction "1_1") (pintype "passive"))
    )
    (net (code "128") (name "Net-(LD4A-A)") (class "Default")
      (node (ref "LD4") (pin "2") (pinfunction "A_2") (pintype "passive"))
      (node (ref "R113") (pin "2") (pinfunction "2_2") (pintype "passive"))
    )
    (net (code "129") (name "Net-(LD4B-A)") (class "Default")
      (node (ref "LD4") (pin "4") (pinfunction "A_4") (pintype "passive"))
      (node (ref "R114") (pin "2") (pinfunction "2_2") (pintype "passive"))
    )
    (net (code "130") (name "Net-(LD4C-A)") (class "Default")
      (node (ref "LD4") (pin "6") (pinfunction "A_6") (pintype "passive"))
      (node (ref "R115") (pin "2") (pinfunction "2_2") (pintype "passive"))
    )
    (net (code "131") (name "Net-(LD4D-A)") (class "Default")
      (node (ref "LD4") (pin "8") (pinfunction "A_8") (pintype "passive"))
      (node (ref "R119") (pin "2") (pinfunction "2_2") (pintype "passive"))
    )
    (net (code "132") (name "Net-(LD5A-A)") (class "Default")
      (node (ref "LD5") (pin "2") (pinfunction "A_2") (pintype "passive"))
      (node (ref "R120") (pin "2") (pinfunction "2_2") (pintype "passive"))
    )
    (net (code "133") (name "Net-(LD5B-A)") (class "Default")
      (node (ref "LD5") (pin "4") (pinfunction "A_4") (pintype "passive"))
      (node (ref "R121") (pin "2") (pinfunction "2_2") (pintype "passive"))
    )
    (net (code "134") (name "Net-(LD5C-A)") (class "Default")
      (node (ref "LD5") (pin "6") (pinfunction "A_6") (pintype "passive"))
      (node (ref "R122") (pin "2") (pinfunction "2_2") (pintype "passive"))
    )
    (net (code "135") (name "Net-(LD5D-A)") (class "Default")
      (node (ref "LD5") (pin "8") (pinfunction "A_8") (pintype "passive"))
      (node (ref "R123") (pin "2") (pinfunction "2_2") (pintype "passive"))
    )
    (net (code "136") (name "P3V3") (class "Default")
      (node (ref "C96") (pin "2") (pinfunction "2_2") (pintype "passive"))
      (node (ref "IC19") (pin "4") (pinfunction "VCC_4") (pintype "power_in"))
      (node (ref "IC23") (pin "10") (pinfunction "~{SRCLR}_10") (pintype "input"))
      (node (ref "IC23") (pin "16") (pinfunction "VCC_16") (pintype "power_in"))
    )
    (net (code "137") (name "P13V0_SCSI") (class "Default")
      (node (ref "J1") (pin "18") (pinfunction "18_18") (pintype "bidirectional"))
      (node (ref "J3") (pin "25") (pinfunction "25_25") (pintype "bidirectional"))
      (node (ref "J4") (pin "25") (pinfunction "25_25") (pintype "bidirectional"))
      (node (ref "J5") (pin "25") (pinfunction "25_25") (pintype "bidirectional"))
      (node (ref "J7") (pin "25") (pinfunction "25_25") (pintype "bidirectional"))
    )
    (net (code "138") (name "unconnected-(IC23-QH'-Pad9)") (class "Default")
      (node (ref "IC23") (pin "9") (pinfunction "QH'_9") (pintype "output"))
    )
  )
)
